# v0_9_0.net
KiCad netlist of a schematic drawn in EAGLE
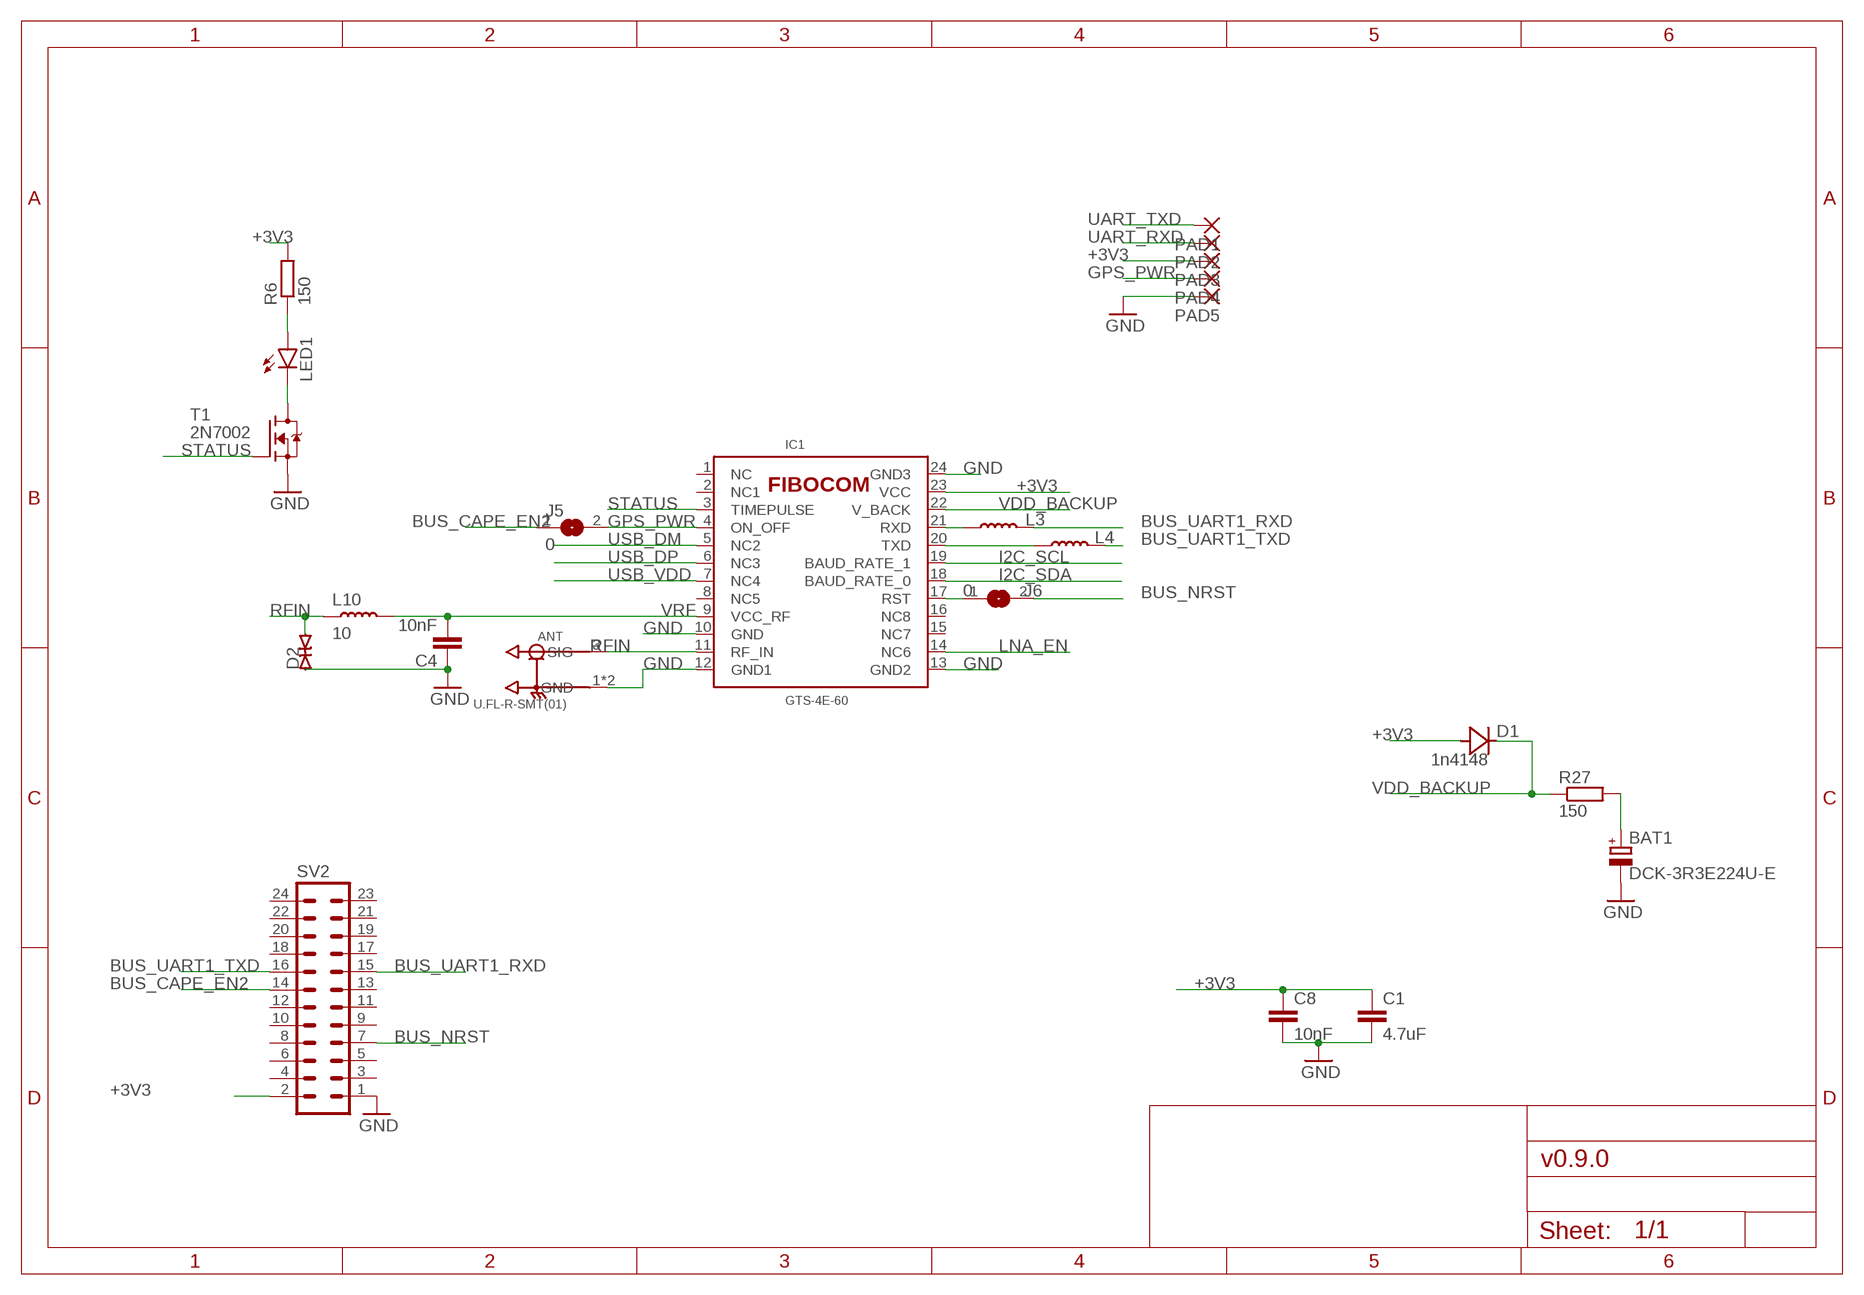
[diagram p0: schematic, sheet 1]

(export (version "E")
  (design (tool "Eeschema 10.0.6"))
  (components
    (comp (ref "ANT")
      (value "U.FL-R-SMT(01)")
      (footprint "eagle-import:HRS_U.FL-R-SMT(01)")
      (fields (field (name "MF") "Hirose") (field (name "MP") "U.FL-R-SMT_01_"))
      (libsource (lib "eagle-import") (part "U.FL-R-SMT(01)"))
    )
    (comp (ref "BAT1")
      (value "DCK-3R3E224U-E")
      (footprint "eagle-import:621")
      (libsource (lib "eagle-import") (part "DCK-3R3E224U-E"))
    )
    (comp (ref "C1")
      (value "4.7uF")
      (footprint "eagle-import:C0603")
      (libsource (lib "eagle-import") (part "CAP-0603"))
    )
    (comp (ref "C4")
      (value "10nF")
      (footprint "eagle-import:C0402K")
      (libsource (lib "eagle-import") (part "CAP-0402"))
    )
    (comp (ref "C8")
      (value "10nF")
      (footprint "eagle-import:C0603")
      (libsource (lib "eagle-import") (part "CAP-0603"))
    )
    (comp (ref "D1")
      (value "1n4148")
      (footprint "eagle-import:SOD323")
      (libsource (lib "eagle-import") (part "1N4148WS"))
    )
    (comp (ref "D2")
      (value "ESD9B5.0ST5G")
      (footprint "eagle-import:SOD1006X40")
      (libsource (lib "eagle-import") (part "ESD9B5.0ST5G"))
    )
    (comp (ref "IC1")
      (value "GTS-4E-60")
      (footprint "eagle-import:_GTS_4E_60")
      (libsource (lib "eagle-import") (part "GTS-4E-60"))
    )
    (comp (ref "J5")
      (value "0")
      (footprint "eagle-import:C0603")
      (libsource (lib "eagle-import") (part "JUMP-0603"))
    )
    (comp (ref "J6")
      (value "0")
      (footprint "eagle-import:C0603")
      (libsource (lib "eagle-import") (part "JUMP-0603"))
    )
    (comp (ref "L3")
      (value "blm15")
      (footprint "eagle-import:L0402")
      (libsource (lib "eagle-import") (part "IND-0402"))
    )
    (comp (ref "L4")
      (value "blm15")
      (footprint "eagle-import:L0402")
      (libsource (lib "eagle-import") (part "IND-0402"))
    )
    (comp (ref "L10")
      (value "10")
      (footprint "eagle-import:L0402")
      (libsource (lib "eagle-import") (part "IND-0402"))
    )
    (comp (ref "LED1")
      (value "LEDCHIP-LED0603")
      (footprint "eagle-import:CHIP-LED0603")
      (libsource (lib "eagle-import") (part "LEDCHIP-LED0603"))
    )
    (comp (ref "PAD1")
      (value "1,6/0,9")
      (footprint "eagle-import:1,6_0,9")
      (libsource (lib "eagle-import") (part "1,6/0,9"))
    )
    (comp (ref "PAD2")
      (value "1,6/0,9")
      (footprint "eagle-import:1,6_0,9")
      (libsource (lib "eagle-import") (part "1,6/0,9"))
    )
    (comp (ref "PAD3")
      (value "1,6/0,9")
      (footprint "eagle-import:1,6_0,9")
      (libsource (lib "eagle-import") (part "1,6/0,9"))
    )
    (comp (ref "PAD4")
      (value "1,6/0,9")
      (footprint "eagle-import:1,6_0,9")
      (libsource (lib "eagle-import") (part "1,6/0,9"))
    )
    (comp (ref "PAD5")
      (value "1,6/0,9")
      (footprint "eagle-import:1,6_0,9")
      (libsource (lib "eagle-import") (part "1,6/0,9"))
    )
    (comp (ref "R6")
      (value "150")
      (footprint "eagle-import:R0603")
      (libsource (lib "eagle-import") (part "RES-0603"))
    )
    (comp (ref "R27")
      (value "150")
      (footprint "eagle-import:R0603")
      (libsource (lib "eagle-import") (part "RES-0603"))
    )
    (comp (ref "SV2")
      (value "MA12-2")
      (footprint "eagle-import:MA12-2")
      (libsource (lib "eagle-import") (part "MA12-2"))
    )
    (comp (ref "T1")
      (value "2N7002")
      (footprint "eagle-import:SOT95P240X110-3")
      (libsource (lib "eagle-import") (part "2N7002"))
    )
  )
  (nets
    (net (code "1") (name "/+3V3") (class "Default")
      (node (ref "C1") (pin "1") (pinfunction "1_1") (pintype "passive"))
      (node (ref "C8") (pin "1") (pinfunction "1_1") (pintype "passive"))
      (node (ref "D1") (pin "A") (pinfunction "A_A") (pintype "passive"))
      (node (ref "IC1") (pin "23") (pinfunction "VCC_23") (pintype "bidirectional"))
      (node (ref "PAD3") (pin "1") (pinfunction "P_1") (pintype "passive"))
      (node (ref "R6") (pin "2") (pinfunction "2_2") (pintype "passive"))
      (node (ref "SV2") (pin "2") (pinfunction "2_2") (pintype "passive"))
    )
    (net (code "2") (name "/BUS_CAPE_EN2") (class "Default")
      (node (ref "J5") (pin "1") (pinfunction "1_1") (pintype "passive"))
      (node (ref "SV2") (pin "14") (pinfunction "14_14") (pintype "passive"))
    )
    (net (code "3") (name "/BUS_NRST") (class "Default")
      (node (ref "J6") (pin "2") (pinfunction "2_2") (pintype "passive"))
      (node (ref "SV2") (pin "7") (pinfunction "7_7") (pintype "passive"))
    )
    (net (code "4") (name "/BUS_UART1_RXD") (class "Default")
      (node (ref "L3") (pin "2") (pinfunction "2_2") (pintype "passive"))
      (node (ref "SV2") (pin "15") (pinfunction "15_15") (pintype "passive"))
    )
    (net (code "5") (name "/BUS_UART1_TXD") (class "Default")
      (node (ref "L4") (pin "2") (pinfunction "2_2") (pintype "passive"))
      (node (ref "SV2") (pin "16") (pinfunction "16_16") (pintype "passive"))
    )
    (net (code "6") (name "/GPS_PWR") (class "Default")
      (node (ref "IC1") (pin "4") (pinfunction "ON_OFF_4") (pintype "bidirectional"))
      (node (ref "J5") (pin "2") (pinfunction "2_2") (pintype "passive"))
      (node (ref "PAD4") (pin "1") (pinfunction "P_1") (pintype "passive"))
    )
    (net (code "7") (name "/I2C_SCL") (class "Default")
      (node (ref "IC1") (pin "19") (pinfunction "BAUD_RATE_1_19") (pintype "bidirectional"))
    )
    (net (code "8") (name "/I2C_SDA") (class "Default")
      (node (ref "IC1") (pin "18") (pinfunction "BAUD_RATE_0_18") (pintype "bidirectional"))
    )
    (net (code "9") (name "/LNA_EN") (class "Default")
      (node (ref "IC1") (pin "14") (pinfunction "NC6_14") (pintype "bidirectional"))
    )
    (net (code "10") (name "/RFIN") (class "Default")
      (node (ref "ANT") (pin "3") (pinfunction "SIG_3") (pintype "passive"))
      (node (ref "D2") (pin "2") (pinfunction "C_2") (pintype "passive"))
      (node (ref "IC1") (pin "11") (pinfunction "RF_IN_11") (pintype "bidirectional"))
      (node (ref "L10") (pin "1") (pinfunction "1_1") (pintype "passive"))
    )
    (net (code "11") (name "/STATUS") (class "Default")
      (node (ref "IC1") (pin "3") (pinfunction "TIMEPULSE_3") (pintype "bidirectional"))
      (node (ref "T1") (pin "1") (pinfunction "G_1") (pintype "passive"))
    )
    (net (code "12") (name "/UART_RXD") (class "Default")
      (node (ref "IC1") (pin "20") (pinfunction "TXD_20") (pintype "bidirectional"))
      (node (ref "L4") (pin "1") (pinfunction "1_1") (pintype "passive"))
      (node (ref "PAD2") (pin "1") (pinfunction "P_1") (pintype "passive"))
    )
    (net (code "13") (name "/UART_TXD") (class "Default")
      (node (ref "IC1") (pin "21") (pinfunction "RXD_21") (pintype "bidirectional"))
      (node (ref "L3") (pin "1") (pinfunction "1_1") (pintype "passive"))
      (node (ref "PAD1") (pin "1") (pinfunction "P_1") (pintype "passive"))
    )
    (net (code "14") (name "/USB_DM") (class "Default")
      (node (ref "IC1") (pin "5") (pinfunction "NC2_5") (pintype "bidirectional"))
    )
    (net (code "15") (name "/USB_DP") (class "Default")
      (node (ref "IC1") (pin "6") (pinfunction "NC3_6") (pintype "bidirectional"))
    )
    (net (code "16") (name "/USB_VDD") (class "Default")
      (node (ref "IC1") (pin "7") (pinfunction "NC4_7") (pintype "bidirectional"))
    )
    (net (code "17") (name "/VDD_BACKUP") (class "Default")
      (node (ref "D1") (pin "K") (pinfunction "C_K") (pintype "passive"))
      (node (ref "IC1") (pin "22") (pinfunction "V_BACK_22") (pintype "bidirectional"))
      (node (ref "R27") (pin "1") (pinfunction "1_1") (pintype "passive"))
    )
    (net (code "18") (name "/VRF") (class "Default")
      (node (ref "C4") (pin "2") (pinfunction "2_2") (pintype "passive"))
      (node (ref "IC1") (pin "9") (pinfunction "VCC_RF_9") (pintype "bidirectional"))
      (node (ref "L10") (pin "2") (pinfunction "2_2") (pintype "passive"))
    )
    (net (code "19") (name "GND") (class "Default")
      (node (ref "ANT") (pin "1") (pinfunction "GND_1") (pintype "passive"))
      (node (ref "ANT") (pin "2") (pinfunction "GND_2") (pintype "passive"))
      (node (ref "BAT1") (pin "-") (pinfunction "-_-") (pintype "passive"))
      (node (ref "C1") (pin "2") (pinfunction "2_2") (pintype "passive"))
      (node (ref "C4") (pin "1") (pinfunction "1_1") (pintype "passive"))
      (node (ref "C8") (pin "2") (pinfunction "2_2") (pintype "passive"))
      (node (ref "D2") (pin "1") (pinfunction "A_1") (pintype "passive"))
      (node (ref "IC1") (pin "10") (pinfunction "GND_10") (pintype "bidirectional"))
      (node (ref "IC1") (pin "12") (pinfunction "GND1_12") (pintype "bidirectional"))
      (node (ref "IC1") (pin "13") (pinfunction "GND2_13") (pintype "bidirectional"))
      (node (ref "IC1") (pin "24") (pinfunction "GND3_24") (pintype "bidirectional"))
      (node (ref "PAD5") (pin "1") (pinfunction "P_1") (pintype "passive"))
      (node (ref "SV2") (pin "1") (pinfunction "1_1") (pintype "passive"))
      (node (ref "T1") (pin "2") (pinfunction "S_2") (pintype "passive"))
    )
    (net (code "20") (name "Net-(BAT1-Pad+)") (class "Default")
      (node (ref "BAT1") (pin "+") (pinfunction "+_+") (pintype "passive"))
      (node (ref "R27") (pin "2") (pinfunction "2_2") (pintype "passive"))
    )
    (net (code "21") (name "Net-(IC1-RST)") (class "Default")
      (node (ref "IC1") (pin "17") (pinfunction "RST_17") (pintype "bidirectional"))
      (node (ref "J6") (pin "1") (pinfunction "1_1") (pintype "passive"))
    )
    (net (code "22") (name "Net-(LED1-PadA)") (class "Default")
      (node (ref "LED1") (pin "A") (pinfunction "A_A") (pintype "passive"))
      (node (ref "R6") (pin "1") (pinfunction "1_1") (pintype "passive"))
    )
    (net (code "23") (name "Net-(T1-D)") (class "Default")
      (node (ref "LED1") (pin "C") (pinfunction "C_C") (pintype "passive"))
      (node (ref "T1") (pin "3") (pinfunction "D_3") (pintype "passive"))
    )
    (net (code "24") (name "unconnected-(IC1-NC-Pad1)") (class "Default")
      (node (ref "IC1") (pin "1") (pinfunction "NC_1") (pintype "bidirectional"))
    )
    (net (code "25") (name "unconnected-(IC1-NC1-Pad2)") (class "Default")
      (node (ref "IC1") (pin "2") (pinfunction "NC1_2") (pintype "bidirectional"))
    )
    (net (code "26") (name "unconnected-(IC1-NC5-Pad8)") (class "Default")
      (node (ref "IC1") (pin "8") (pinfunction "NC5_8") (pintype "bidirectional"))
    )
    (net (code "27") (name "unconnected-(IC1-NC7-Pad15)") (class "Default")
      (node (ref "IC1") (pin "15") (pinfunction "NC7_15") (pintype "bidirectional"))
    )
    (net (code "28") (name "unconnected-(IC1-NC8-Pad16)") (class "Default")
      (node (ref "IC1") (pin "16") (pinfunction "NC8_16") (pintype "bidirectional"))
    )
    (net (code "29") (name "unconnected-(SV2-Pad3)") (class "Default")
      (node (ref "SV2") (pin "3") (pinfunction "3_3") (pintype "passive"))
    )
    (net (code "30") (name "unconnected-(SV2-Pad4)") (class "Default")
      (node (ref "SV2") (pin "4") (pinfunction "4_4") (pintype "passive"))
    )
    (net (code "31") (name "unconnected-(SV2-Pad5)") (class "Default")
      (node (ref "SV2") (pin "5") (pinfunction "5_5") (pintype "passive"))
    )
    (net (code "32") (name "unconnected-(SV2-Pad6)") (class "Default")
      (node (ref "SV2") (pin "6") (pinfunction "6_6") (pintype "passive"))
    )
    (net (code "33") (name "unconnected-(SV2-Pad8)") (class "Default")
      (node (ref "SV2") (pin "8") (pinfunction "8_8") (pintype "passive"))
    )
    (net (code "34") (name "unconnected-(SV2-Pad9)") (class "Default")
      (node (ref "SV2") (pin "9") (pinfunction "9_9") (pintype "passive"))
    )
    (net (code "35") (name "unconnected-(SV2-Pad10)") (class "Default")
      (node (ref "SV2") (pin "10") (pinfunction "10_10") (pintype "passive"))
    )
    (net (code "36") (name "unconnected-(SV2-Pad11)") (class "Default")
      (node (ref "SV2") (pin "11") (pinfunction "11_11") (pintype "passive"))
    )
    (net (code "37") (name "unconnected-(SV2-Pad12)") (class "Default")
      (node (ref "SV2") (pin "12") (pinfunction "12_12") (pintype "passive"))
    )
    (net (code "38") (name "unconnected-(SV2-Pad13)") (class "Default")
      (node (ref "SV2") (pin "13") (pinfunction "13_13") (pintype "passive"))
    )
    (net (code "39") (name "unconnected-(SV2-Pad17)") (class "Default")
      (node (ref "SV2") (pin "17") (pinfunction "17_17") (pintype "passive"))
    )
    (net (code "40") (name "unconnected-(SV2-Pad18)") (class "Default")
      (node (ref "SV2") (pin "18") (pinfunction "18_18") (pintype "passive"))
    )
    (net (code "41") (name "unconnected-(SV2-Pad19)") (class "Default")
      (node (ref "SV2") (pin "19") (pinfunction "19_19") (pintype "passive"))
    )
    (net (code "42") (name "unconnected-(SV2-Pad20)") (class "Default")
      (node (ref "SV2") (pin "20") (pinfunction "20_20") (pintype "passive"))
    )
    (net (code "43") (name "unconnected-(SV2-Pad21)") (class "Default")
      (node (ref "SV2") (pin "21") (pinfunction "21_21") (pintype "passive"))
    )
    (net (code "44") (name "unconnected-(SV2-Pad22)") (class "Default")
      (node (ref "SV2") (pin "22") (pinfunction "22_22") (pintype "passive"))
    )
    (net (code "45") (name "unconnected-(SV2-Pad23)") (class "Default")
      (node (ref "SV2") (pin "23") (pinfunction "23_23") (pintype "passive"))
    )
    (net (code "46") (name "unconnected-(SV2-Pad24)") (class "Default")
      (node (ref "SV2") (pin "24") (pinfunction "24_24") (pintype "passive"))
    )
  )
)
